# Neg5V.net
KiCad netlist of a schematic drawn in Altium Designer
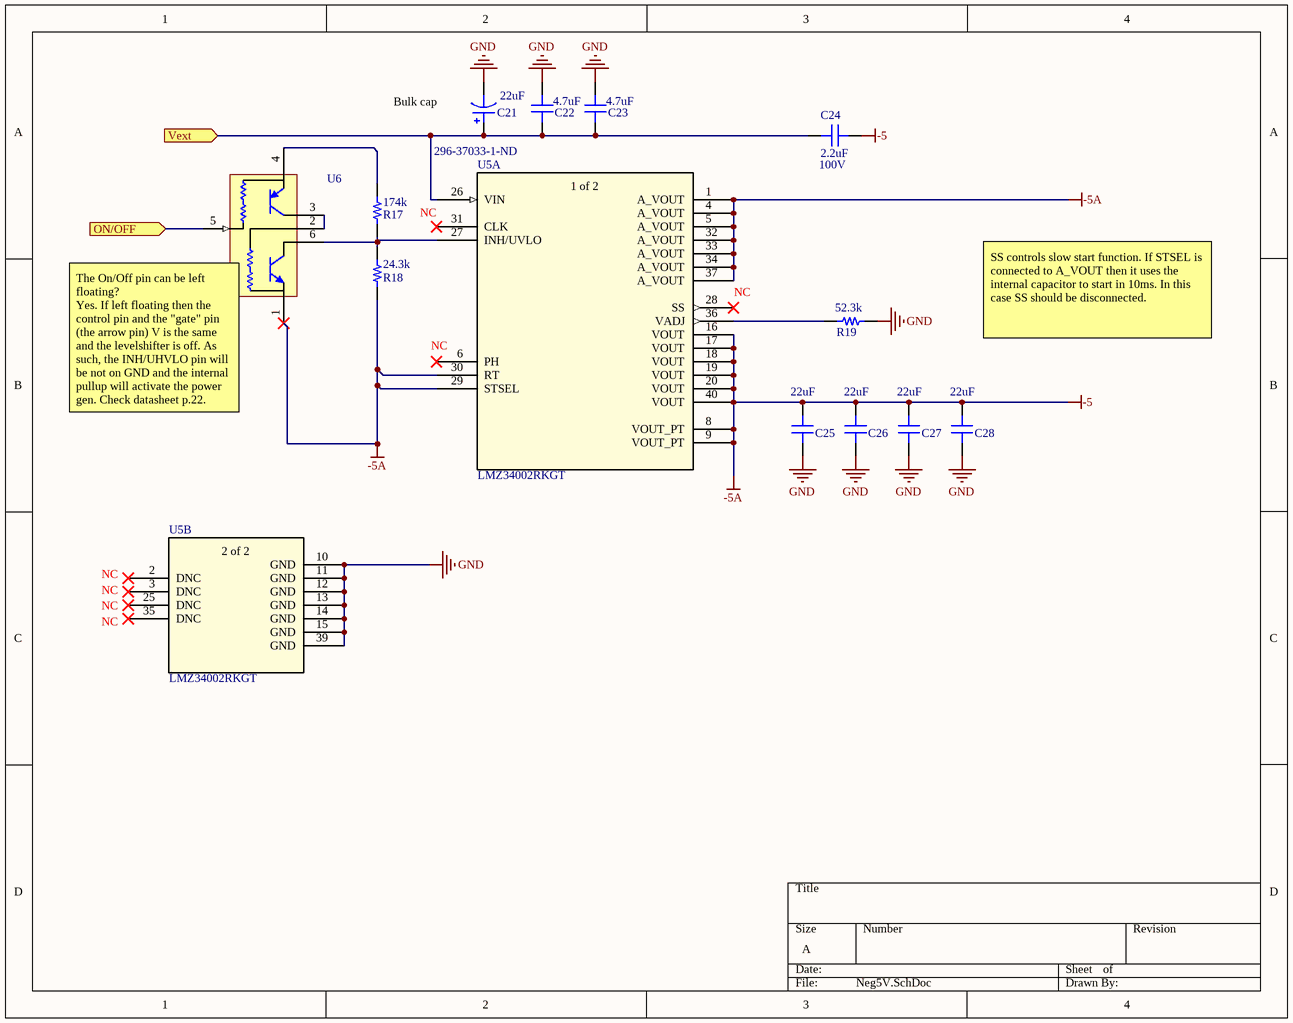
[diagram p0: Neg5V.SchDoc]

(export (version "E")
  (design (tool "Eeschema 10.0.6"))
  (components
    (comp (ref "C21")
      (value "22uF")
      (footprint "CAP AL TH D8 L3.5 H11.5")
      (description "CAP ALUM 22UF 20% 100V RADIAL")
      (fields
        (field (name "PART NUMBER") "EEU-FC2A220")
        (field (name "MANUFACTURER") "Panasonic Electronic Components")
      )
      (libsource (lib "Celestial Library Database") (part "Polarised Capacitor"))
    )
    (comp (ref "C22")
      (value "4.7uF")
      (footprint "CAP 1206/3216 - 1.0MM")
      (description "CAP CER 4.7UF 50V X5R 1206")
      (fields
        (field (name "PART NUMBER") "C3216X5R1H475K085AB")
        (field (name "MANUFACTURER") "TDK Corporation")
      )
      (libsource (lib "Celestial Library Database") (part "Capacitor"))
    )
    (comp (ref "C23")
      (value "4.7uF")
      (footprint "CAP 1206/3216 - 1.0MM")
      (description "CAP CER 4.7UF 50V X5R 1206")
      (fields
        (field (name "PART NUMBER") "C3216X5R1H475K085AB")
        (field (name "MANUFACTURER") "TDK Corporation")
      )
      (libsource (lib "Celestial Library Database") (part "Capacitor"))
    )
    (comp (ref "C24")
      (value "2.2uF")
      (footprint "CAP 1206/3216")
      (description "CAP CER 2.2UF 100V X7R 1206")
      (fields
        (field (name "PART NUMBER") "CL31B225KCHSNNE")
        (field (name "MANUFACTURER") "Samsung Electro-Mechanics America, Inc.")
      )
      (libsource (lib "Celestial Library Database") (part "Capacitor"))
    )
    (comp (ref "C25")
      (value "22uF")
      (footprint "CAP 1206/3216")
      (description "CAP CER 22UF 25V X5R 1206")
      (fields
        (field (name "PART NUMBER") "CL31A226KAHNNNE")
        (field (name "MANUFACTURER") "Samsung Electro-Mechanics America, Inc.")
      )
      (libsource (lib "Celestial Library Database") (part "Capacitor"))
    )
    (comp (ref "C26")
      (value "22uF")
      (footprint "CAP 1206/3216")
      (description "CAP CER 22UF 25V X5R 1206")
      (fields
        (field (name "PART NUMBER") "CL31A226KAHNNNE")
        (field (name "MANUFACTURER") "Samsung Electro-Mechanics America, Inc.")
      )
      (libsource (lib "Celestial Library Database") (part "Capacitor"))
    )
    (comp (ref "C27")
      (value "22uF")
      (footprint "CAP 1206/3216")
      (description "CAP CER 22UF 25V X5R 1206")
      (fields
        (field (name "PART NUMBER") "CL31A226KAHNNNE")
        (field (name "MANUFACTURER") "Samsung Electro-Mechanics America, Inc.")
      )
      (libsource (lib "Celestial Library Database") (part "Capacitor"))
    )
    (comp (ref "C28")
      (value "22uF")
      (footprint "CAP 1206/3216")
      (description "CAP CER 22UF 25V X5R 1206")
      (fields
        (field (name "PART NUMBER") "CL31A226KAHNNNE")
        (field (name "MANUFACTURER") "Samsung Electro-Mechanics America, Inc.")
      )
      (libsource (lib "Celestial Library Database") (part "Capacitor"))
    )
    (comp (ref "R17")
      (value "174k")
      (footprint "RES 0805/2012")
      (description "RES SMD 174K OHM 1% 1/8W 0805")
      (fields
        (field (name "PART NUMBER") "ERJ-6ENF1743V")
        (field (name "MANUFACTURER") "Panasonic Electronic Components")
      )
      (libsource (lib "Celestial Library Database") (part "Resistor"))
    )
    (comp (ref "R18")
      (value "24.3k")
      (footprint "RES 0805/2012")
      (description "RES SMD 24.3K OHM 1% 1/8W 0805")
      (fields
        (field (name "PART NUMBER") "ERJ-6ENF2432V")
        (field (name "MANUFACTURER") "Panasonic Electronic Components")
      )
      (libsource (lib "Celestial Library Database") (part "Resistor"))
    )
    (comp (ref "R19")
      (value "52.3k")
      (footprint "RES 0805/2012")
      (description "RES SMD 52.3K OHM 1% 1/8W 0805")
      (fields
        (field (name "PART NUMBER") "ERJ-6ENF5232V")
        (field (name "MANUFACTURER") "Panasonic Electronic Components")
      )
      (libsource (lib "Celestial Library Database") (part "Resistor"))
    )
    (comp (ref "U5")
      (value "LMZ34002RKGT")
      (footprint "RKG41")
      (description "No Description Available")
      (fields
        (field (name "SUPPLIER PART NUMBER 1") "296-37033-1-ND")
        (field (name "COPYRIGHT") "Copyright (C) 2018 Accelerated Designs. All rights reserved")
      )
      (libsource (lib "Voltage Regulators Switchmode") (part "LMZ34002RKGT"))
    )
    (comp (ref "U6")
      (value "DCX144EH-7")
      (footprint "SOT-563")
      (description "TRANS PREBIAS NPN/PNP SOT563")
      (fields (field (name "MANUFACTURER") "Diodes Incorporated"))
      (libsource (lib "Celestial Library Database") (part "PNP/NPN Combination"))
    )
  )
  (nets
    (net (code "1") (name "-5") (class "Default")
      (node (ref "C24") (pin "1") (pinfunction "1_1") (pintype "passive"))
      (node (ref "C25") (pin "2") (pinfunction "2_2") (pintype "passive"))
      (node (ref "C26") (pin "2") (pinfunction "2_2") (pintype "passive"))
      (node (ref "C27") (pin "2") (pinfunction "2_2") (pintype "passive"))
      (node (ref "C28") (pin "2") (pinfunction "2_2") (pintype "passive"))
      (node (ref "R18") (pin "1") (pinfunction "1_1") (pintype "passive"))
      (node (ref "U5") (pin "1") (pinfunction "A_VOUT_1") (pintype "power_in"))
      (node (ref "U5") (pin "16") (pinfunction "VOUT_16") (pintype "power_in"))
      (node (ref "U5") (pin "17") (pinfunction "VOUT_17") (pintype "power_in"))
      (node (ref "U5") (pin "18") (pinfunction "VOUT_18") (pintype "power_in"))
      (node (ref "U5") (pin "19") (pinfunction "VOUT_19") (pintype "power_in"))
      (node (ref "U5") (pin "20") (pinfunction "VOUT_20") (pintype "power_in"))
      (node (ref "U5") (pin "29") (pinfunction "STSEL_29") (pintype "passive"))
      (node (ref "U5") (pin "30") (pinfunction "RT_30") (pintype "passive"))
      (node (ref "U5") (pin "32") (pinfunction "A_VOUT_32") (pintype "power_in"))
      (node (ref "U5") (pin "33") (pinfunction "A_VOUT_33") (pintype "power_in"))
      (node (ref "U5") (pin "34") (pinfunction "A_VOUT_34") (pintype "power_in"))
      (node (ref "U5") (pin "37") (pinfunction "A_VOUT_37") (pintype "power_in"))
      (node (ref "U5") (pin "4") (pinfunction "A_VOUT_4") (pintype "power_in"))
      (node (ref "U5") (pin "40") (pinfunction "VOUT_40") (pintype "power_in"))
      (node (ref "U5") (pin "5") (pinfunction "A_VOUT_5") (pintype "power_in"))
      (node (ref "U5") (pin "8") (pinfunction "VOUT_PT_8") (pintype "passive"))
      (node (ref "U5") (pin "9") (pinfunction "VOUT_PT_9") (pintype "passive"))
      (node (ref "U6") (pin "1") (pintype "open_emitter"))
    )
    (net (code "2") (name "/ON{slash}OFF") (class "Default") (node (ref "U6") (pin "5") (pintype "input")))
    (net (code "3") (name "/Vext") (class "Default")
      (node (ref "C21") (pin "1") (pinfunction "1_1") (pintype "passive"))
      (node (ref "C22") (pin "1") (pinfunction "1_1") (pintype "passive"))
      (node (ref "C23") (pin "1") (pinfunction "1_1") (pintype "passive"))
      (node (ref "C24") (pin "2") (pinfunction "2_2") (pintype "passive"))
      (node (ref "U5") (pin "26") (pinfunction "VIN_26") (pintype "input"))
    )
    (net (code "4") (name "GND") (class "Default")
      (node (ref "C21") (pin "2") (pinfunction "2_2") (pintype "passive"))
      (node (ref "C22") (pin "2") (pinfunction "2_2") (pintype "passive"))
      (node (ref "C23") (pin "2") (pinfunction "2_2") (pintype "passive"))
      (node (ref "C25") (pin "1") (pinfunction "1_1") (pintype "passive"))
      (node (ref "C26") (pin "1") (pinfunction "1_1") (pintype "passive"))
      (node (ref "C27") (pin "1") (pinfunction "1_1") (pintype "passive"))
      (node (ref "C28") (pin "1") (pinfunction "1_1") (pintype "passive"))
      (node (ref "R19") (pin "2") (pinfunction "2_2") (pintype "passive"))
      (node (ref "U5") (pin "10") (pinfunction "GND_10") (pintype "power_in"))
      (node (ref "U5") (pin "11") (pinfunction "GND_11") (pintype "power_in"))
      (node (ref "U5") (pin "12") (pinfunction "GND_12") (pintype "power_in"))
      (node (ref "U5") (pin "13") (pinfunction "GND_13") (pintype "power_in"))
      (node (ref "U5") (pin "14") (pinfunction "GND_14") (pintype "power_in"))
      (node (ref "U5") (pin "15") (pinfunction "GND_15") (pintype "power_in"))
      (node (ref "U5") (pin "39") (pinfunction "GND_39") (pintype "power_in"))
    )
    (net (code "5") (name "Net-(R17-Pad2)") (class "Default")
      (node (ref "R17") (pin "2") (pinfunction "2_2") (pintype "passive"))
      (node (ref "U6") (pin "4") (pintype "open_emitter"))
    )
    (net (code "6") (name "Net-(U5A-INH{slash}UVLO)") (class "Default")
      (node (ref "R17") (pin "1") (pinfunction "1_1") (pintype "passive"))
      (node (ref "R18") (pin "2") (pinfunction "2_2") (pintype "passive"))
      (node (ref "U5") (pin "27") (pinfunction "INH/UVLO_27") (pintype "passive"))
      (node (ref "U6") (pin "6") (pintype "open_collector"))
    )
    (net (code "7") (name "Net-(U5A-VADJ)") (class "Default")
      (node (ref "R19") (pin "1") (pinfunction "1_1") (pintype "passive"))
      (node (ref "U5") (pin "36") (pinfunction "VADJ_36") (pintype "output"))
    )
    (net (code "8") (name "Net-(U6-Pad2)") (class "Default")
      (node (ref "U6") (pin "2") (pintype "open_collector"))
      (node (ref "U6") (pin "3") (pintype "open_collector"))
    )
    (net (code "9") (name "unconnected-(U5A-CLK-Pad31)") (class "Default")
      (node (ref "U5") (pin "31") (pinfunction "CLK_31") (pintype "passive+no_connect"))
    )
    (net (code "10") (name "unconnected-(U5A-PH-Pad6)") (class "Default")
      (node (ref "U5") (pin "6") (pinfunction "PH_6") (pintype "passive+no_connect"))
    )
    (net (code "11") (name "unconnected-(U5A-SS-Pad28)") (class "Default")
      (node (ref "U5") (pin "28") (pinfunction "SS_28") (pintype "output+no_connect"))
    )
    (net (code "12") (name "unconnected-(U5B-DNC-Pad2)") (class "Default")
      (node (ref "U5") (pin "2") (pinfunction "DNC_2") (pintype "passive+no_connect"))
    )
    (net (code "13") (name "unconnected-(U5B-DNC-Pad3)") (class "Default")
      (node (ref "U5") (pin "3") (pinfunction "DNC_3") (pintype "passive+no_connect"))
    )
    (net (code "14") (name "unconnected-(U5B-DNC-Pad25)") (class "Default")
      (node (ref "U5") (pin "25") (pinfunction "DNC_25") (pintype "passive+no_connect"))
    )
    (net (code "15") (name "unconnected-(U5B-DNC-Pad35)") (class "Default")
      (node (ref "U5") (pin "35") (pinfunction "DNC_35") (pintype "passive+no_connect"))
    )
  )
)
